# Sheet1.net
KiCad netlist of a schematic drawn in Altium Designer
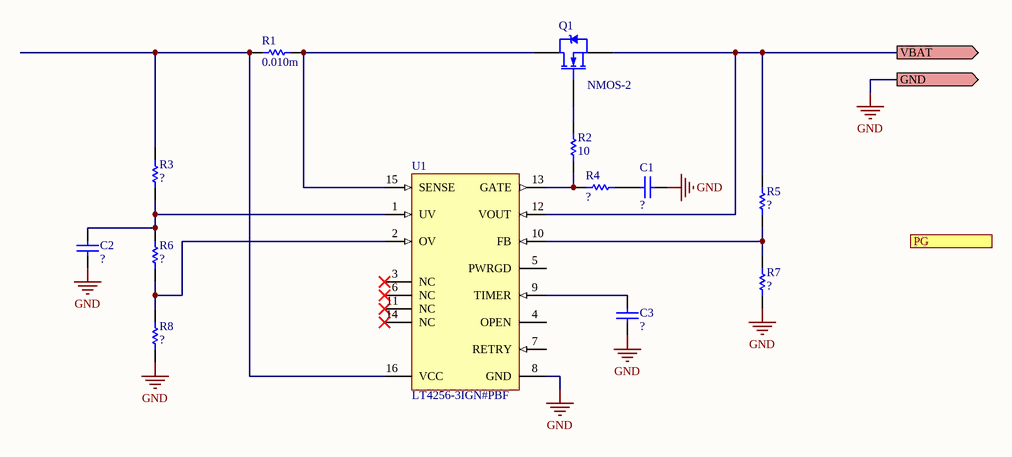
[diagram p0: Sheet1.SchDoc]

(export (version "E")
  (design (tool "Eeschema 10.0.6"))
  (components
    (comp (ref "C1")
      (value "?")
      (footprint "RAD-0.3")
      (description "Capacitor")
      (fields (field (name "Comment") "Cap") (field (name "PUBLISHER") "Altium Limited"))
      (libsource (lib "Miscellaneous Devices") (part "Cap"))
    )
    (comp (ref "C2")
      (value "?")
      (footprint "RAD-0.3")
      (description "Capacitor")
      (fields (field (name "Comment") "Cap") (field (name "PUBLISHER") "Altium Limited"))
      (libsource (lib "Miscellaneous Devices") (part "Cap"))
    )
    (comp (ref "C3")
      (value "?")
      (footprint "RAD-0.3")
      (description "Capacitor")
      (fields (field (name "Comment") "Cap") (field (name "PUBLISHER") "Altium Limited"))
      (libsource (lib "Miscellaneous Devices") (part "Cap"))
    )
    (comp (ref "Q1")
      (value "NMOS-2")
      (footprint "TO-220AB")
      (description "N-Channel Power MOSFET")
      (fields (field (name "PUBLISHER") "Altium Limited"))
      (libsource (lib "Miscellaneous Devices") (part "NMOS-2"))
    )
    (comp (ref "R1")
      (value "0.010m")
      (footprint "AXIAL-0.3")
      (description "Resistor")
      (fields (field (name "Comment") "Res1") (field (name "PUBLISHER") "Altium Limited"))
      (libsource (lib "Miscellaneous Devices") (part "Res1"))
    )
    (comp (ref "R2")
      (value "10")
      (footprint "AXIAL-0.3")
      (description "Resistor")
      (fields (field (name "Comment") "Res1") (field (name "PUBLISHER") "Altium Limited"))
      (libsource (lib "Miscellaneous Devices") (part "Res1"))
    )
    (comp (ref "R3")
      (value "?")
      (footprint "AXIAL-0.3")
      (description "Resistor")
      (fields (field (name "Comment") "Res1") (field (name "PUBLISHER") "Altium Limited"))
      (libsource (lib "Miscellaneous Devices") (part "Res1"))
    )
    (comp (ref "R4")
      (value "?")
      (footprint "AXIAL-0.3")
      (description "Resistor")
      (fields (field (name "Comment") "Res1") (field (name "PUBLISHER") "Altium Limited"))
      (libsource (lib "Miscellaneous Devices") (part "Res1"))
    )
    (comp (ref "R5")
      (value "?")
      (footprint "AXIAL-0.3")
      (description "Resistor")
      (fields (field (name "Comment") "Res1") (field (name "PUBLISHER") "Altium Limited"))
      (libsource (lib "Miscellaneous Devices") (part "Res1"))
    )
    (comp (ref "R6")
      (value "?")
      (footprint "AXIAL-0.3")
      (description "Resistor")
      (fields (field (name "Comment") "Res1") (field (name "PUBLISHER") "Altium Limited"))
      (libsource (lib "Miscellaneous Devices") (part "Res1"))
    )
    (comp (ref "R7")
      (value "?")
      (footprint "AXIAL-0.3")
      (description "Resistor")
      (fields (field (name "Comment") "Res1") (field (name "PUBLISHER") "Altium Limited"))
      (libsource (lib "Miscellaneous Devices") (part "Res1"))
    )
    (comp (ref "R8")
      (value "?")
      (footprint "AXIAL-0.3")
      (description "Resistor")
      (fields (field (name "Comment") "Res1") (field (name "PUBLISHER") "Altium Limited"))
      (libsource (lib "Miscellaneous Devices") (part "Res1"))
    )
    (comp (ref "U1")
      (value "LT4256-3IGN#PBF")
      (footprint "LT-GN-16_L")
      (fields (field (name "MANUFACTURER") "Linear Technology"))
      (libsource (lib "Altium Content Vault") (part "LT-LT4256-3-GN-16"))
    )
  )
  (nets
    (net (code "2") (name "/VBAT") (class "Default")
      (node (ref "Q1") (pin "3") (pinfunction "S_3") (pintype "passive"))
      (node (ref "R5") (pin "2") (pinfunction "2_2") (pintype "passive"))
      (node (ref "U1") (pin "12") (pinfunction "VOUT_12") (pintype "input"))
    )
    (net (code "3") (name "GND") (class "Default")
      (node (ref "C1") (pin "1") (pinfunction "1_1") (pintype "passive"))
      (node (ref "C2") (pin "1") (pinfunction "1_1") (pintype "passive"))
      (node (ref "C3") (pin "1") (pinfunction "1_1") (pintype "passive"))
      (node (ref "R7") (pin "1") (pinfunction "1_1") (pintype "passive"))
      (node (ref "R8") (pin "1") (pinfunction "1_1") (pintype "passive"))
      (node (ref "U1") (pin "8") (pinfunction "GND_8") (pintype "power_in"))
    )
    (net (code "4") (name "Net-(C1-Pad2)") (class "Default")
      (node (ref "C1") (pin "2") (pinfunction "2_2") (pintype "passive"))
      (node (ref "R4") (pin "1") (pinfunction "1_1") (pintype "passive"))
    )
    (net (code "5") (name "Net-(Q1-D)") (class "Default")
      (node (ref "Q1") (pin "2") (pinfunction "D_2") (pintype "passive"))
      (node (ref "R1") (pin "2") (pinfunction "2_2") (pintype "passive"))
      (node (ref "U1") (pin "15") (pinfunction "SENSE_15") (pintype "input"))
    )
    (net (code "6") (name "Net-(Q1-G)") (class "Default")
      (node (ref "Q1") (pin "1") (pinfunction "G_1") (pintype "passive"))
      (node (ref "R2") (pin "2") (pinfunction "2_2") (pintype "passive"))
    )
    (net (code "7") (name "Net-(U1-FB)") (class "Default")
      (node (ref "R5") (pin "1") (pinfunction "1_1") (pintype "passive"))
      (node (ref "R7") (pin "2") (pinfunction "2_2") (pintype "passive"))
      (node (ref "U1") (pin "10") (pinfunction "FB_10") (pintype "input"))
    )
    (net (code "8") (name "Net-(U1-GATE)") (class "Default")
      (node (ref "R2") (pin "1") (pinfunction "1_1") (pintype "passive"))
      (node (ref "R4") (pin "2") (pinfunction "2_2") (pintype "passive"))
      (node (ref "U1") (pin "13") (pinfunction "GATE_13") (pintype "output"))
    )
    (net (code "9") (name "Net-(U1-OV)") (class "Default")
      (node (ref "R6") (pin "1") (pinfunction "1_1") (pintype "passive"))
      (node (ref "R8") (pin "2") (pinfunction "2_2") (pintype "passive"))
      (node (ref "U1") (pin "2") (pinfunction "OV_2") (pintype "input"))
    )
    (net (code "10") (name "Net-(U1-TIMER)") (class "Default")
      (node (ref "C3") (pin "2") (pinfunction "2_2") (pintype "passive"))
      (node (ref "U1") (pin "9") (pinfunction "TIMER_9") (pintype "input"))
    )
    (net (code "11") (name "Net-(U1-UV)") (class "Default")
      (node (ref "C2") (pin "2") (pinfunction "2_2") (pintype "passive"))
      (node (ref "R3") (pin "1") (pinfunction "1_1") (pintype "passive"))
      (node (ref "R6") (pin "2") (pinfunction "2_2") (pintype "passive"))
      (node (ref "U1") (pin "1") (pinfunction "UV_1") (pintype "input"))
    )
    (net (code "12") (name "Net-(U1-VCC)") (class "Default")
      (node (ref "R1") (pin "1") (pinfunction "1_1") (pintype "passive"))
      (node (ref "R3") (pin "2") (pinfunction "2_2") (pintype "passive"))
      (node (ref "U1") (pin "16") (pinfunction "VCC_16") (pintype "power_in"))
    )
    (net (code "13") (name "unconnected-(U1-NC-Pad3)") (class "Default")
      (node (ref "U1") (pin "3") (pinfunction "NC_3") (pintype "passive+no_connect"))
    )
    (net (code "14") (name "unconnected-(U1-NC-Pad6)") (class "Default")
      (node (ref "U1") (pin "6") (pinfunction "NC_6") (pintype "passive+no_connect"))
    )
    (net (code "15") (name "unconnected-(U1-NC-Pad11)") (class "Default")
      (node (ref "U1") (pin "11") (pinfunction "NC_11") (pintype "passive+no_connect"))
    )
    (net (code "16") (name "unconnected-(U1-NC-Pad14)") (class "Default")
      (node (ref "U1") (pin "14") (pinfunction "NC_14") (pintype "passive+no_connect"))
    )
    (net (code "17") (name "unconnected-(U1-OPEN-Pad4)") (class "Default")
      (node (ref "U1") (pin "4") (pinfunction "OPEN_4") (pintype "open_collector"))
    )
    (net (code "18") (name "unconnected-(U1-PWRGD-Pad5)") (class "Default")
      (node (ref "U1") (pin "5") (pinfunction "PWRGD_5") (pintype "tri_state"))
    )
    (net (code "19") (name "unconnected-(U1-RETRY-Pad7)") (class "Default")
      (node (ref "U1") (pin "7") (pinfunction "RETRY_7") (pintype "input"))
    )
  )
)
